# wrt54_relay_board.net
KiCad netlist of a schematic drawn in EAGLE
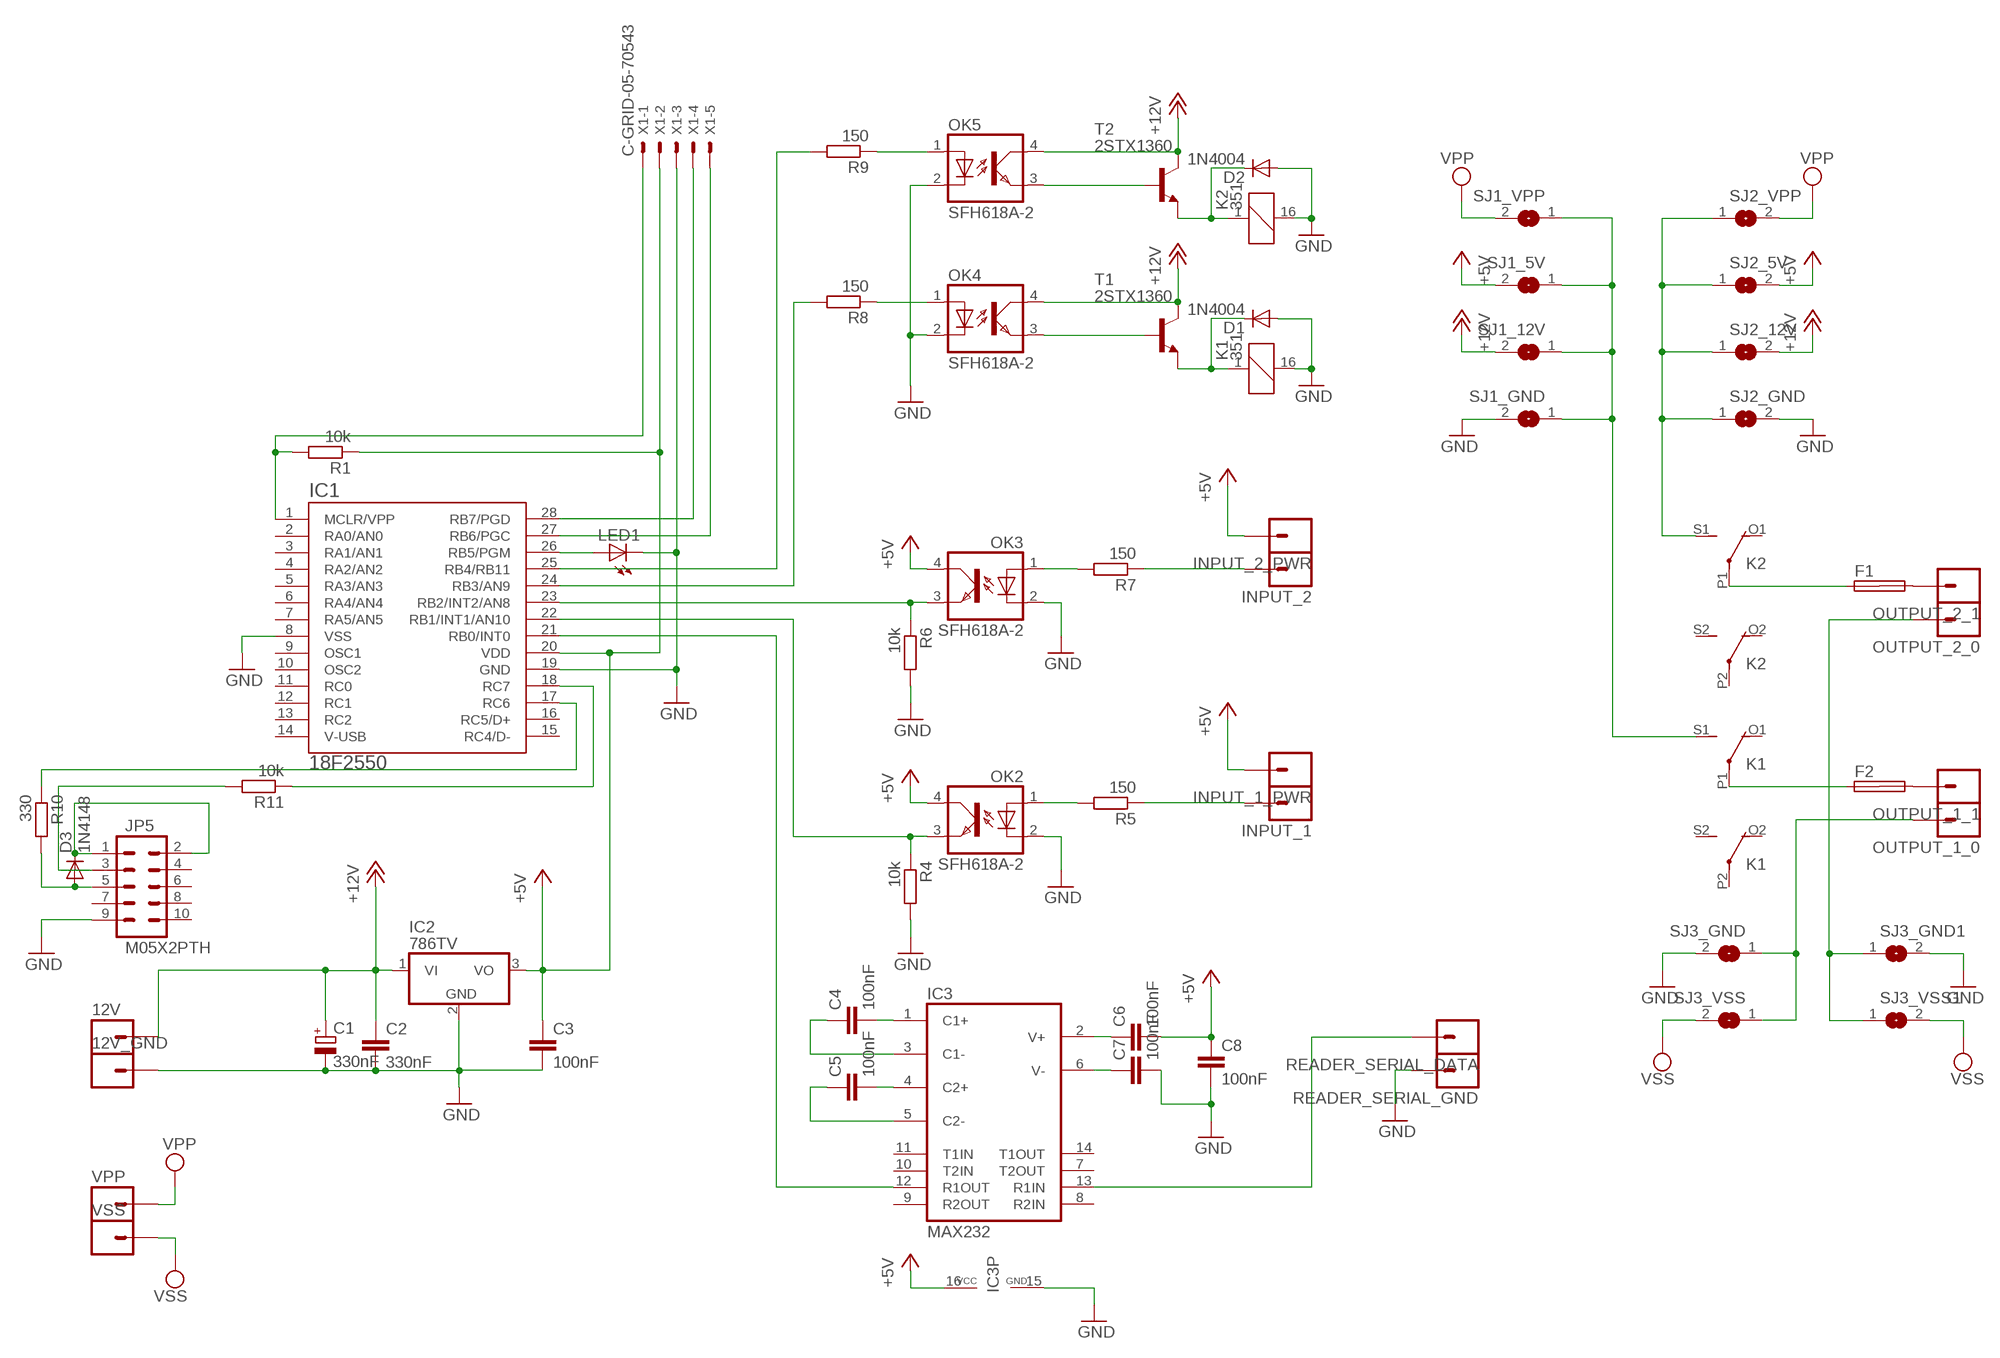
[diagram p0: schematic, sheet 1]

(export (version "E")
  (design (tool "Eeschema 10.0.6"))
  (components
    (comp (ref "12V")
      (value "M01PTH_LONGPAD")
      (footprint "eagle-import:1X01_LONGPAD")
      (libsource (lib "eagle-import") (part "M01PTH_LONGPAD"))
    )
    (comp (ref "12V_GND")
      (value "M01PTH_LONGPAD")
      (footprint "eagle-import:1X01_LONGPAD")
      (libsource (lib "eagle-import") (part "M01PTH_LONGPAD"))
    )
    (comp (ref "C1")
      (value "330nF")
      (footprint "eagle-import:E5-6")
      (libsource (lib "eagle-import") (part "CPOL-EUE5-6"))
    )
    (comp (ref "C2")
      (value "330nF")
      (footprint "eagle-import:C5B2.5")
      (libsource (lib "eagle-import") (part "C5/2.5"))
    )
    (comp (ref "C3")
      (value "100nF")
      (footprint "eagle-import:C5B2.5")
      (libsource (lib "eagle-import") (part "C5/2.5"))
    )
    (comp (ref "C4")
      (value "100nF")
      (footprint "eagle-import:C5B2.5")
      (libsource (lib "eagle-import") (part "C5/2.5"))
    )
    (comp (ref "C5")
      (value "100nF")
      (footprint "eagle-import:C5B2.5")
      (libsource (lib "eagle-import") (part "C5/2.5"))
    )
    (comp (ref "C6")
      (value "100nF")
      (footprint "eagle-import:C5B2.5")
      (libsource (lib "eagle-import") (part "C5/2.5"))
    )
    (comp (ref "C7")
      (value "100nF")
      (footprint "eagle-import:C5B2.5")
      (libsource (lib "eagle-import") (part "C5/2.5"))
    )
    (comp (ref "C8")
      (value "100nF")
      (footprint "eagle-import:C5B2.5")
      (libsource (lib "eagle-import") (part "C5/2.5"))
    )
    (comp (ref "D1")
      (value "1N4004")
      (footprint "eagle-import:DO35-7")
      (libsource (lib "eagle-import") (part "1N4148DO35-7"))
    )
    (comp (ref "D2")
      (value "1N4004")
      (footprint "eagle-import:DO35-7")
      (libsource (lib "eagle-import") (part "1N4148DO35-7"))
    )
    (comp (ref "D3")
      (value "1N4148")
      (footprint "eagle-import:DO35-7")
      (libsource (lib "eagle-import") (part "1N4148DO35-7"))
    )
    (comp (ref "F1")
      (value "SHK20L")
      (footprint "eagle-import:SHK20L")
      (libsource (lib "eagle-import") (part "SHK20L"))
    )
    (comp (ref "F2")
      (value "SHK20L")
      (footprint "eagle-import:SHK20L")
      (libsource (lib "eagle-import") (part "SHK20L"))
    )
    (comp (ref "IC1")
      (value "18F2550")
      (footprint "eagle-import:DIL28")
      (libsource (lib "eagle-import") (part "PIC18F2550DIL-28"))
    )
    (comp (ref "IC2")
      (value "786TV")
      (footprint "eagle-import:TO220V")
      (libsource (lib "eagle-import") (part "78TV6"))
    )
    (comp (ref "IC3")
      (value "MAX232")
      (footprint "eagle-import:DIL16")
      (fields (field (name "MF") "MAXIM") (field (name "MPN") "MAX232ACPE+"))
      (libsource (lib "eagle-import") (part "MAX232"))
    )
    (comp (ref "INPUT_1")
      (value "M01PTH_LONGPAD")
      (footprint "eagle-import:1X01_LONGPAD")
      (libsource (lib "eagle-import") (part "M01PTH_LONGPAD"))
    )
    (comp (ref "INPUT_1_PWR")
      (value "M01PTH_LONGPAD")
      (footprint "eagle-import:1X01_LONGPAD")
      (libsource (lib "eagle-import") (part "M01PTH_LONGPAD"))
    )
    (comp (ref "INPUT_2")
      (value "M01PTH_LONGPAD")
      (footprint "eagle-import:1X01_LONGPAD")
      (libsource (lib "eagle-import") (part "M01PTH_LONGPAD"))
    )
    (comp (ref "INPUT_2_PWR")
      (value "M01PTH_LONGPAD")
      (footprint "eagle-import:1X01_LONGPAD")
      (libsource (lib "eagle-import") (part "M01PTH_LONGPAD"))
    )
    (comp (ref "JP5")
      (value "M05X2PTH")
      (footprint "eagle-import:AVR_ICSP")
      (libsource (lib "eagle-import") (part "M05X2PTH"))
    )
    (comp (ref "K1")
      (value "351")
      (footprint "eagle-import:351")
      (libsource (lib "eagle-import") (part "351"))
    )
    (comp (ref "K2")
      (value "351")
      (footprint "eagle-import:351")
      (libsource (lib "eagle-import") (part "351"))
    )
    (comp (ref "LED1")
      (value "LED5MM")
      (footprint "eagle-import:LED5MM")
      (libsource (lib "eagle-import") (part "LED5MM"))
    )
    (comp (ref "OK2")
      (value "SFH618A-2")
      (footprint "eagle-import:DIP4")
      (libsource (lib "eagle-import") (part "SFH618?A-2"))
    )
    (comp (ref "OK3")
      (value "SFH618A-2")
      (footprint "eagle-import:DIP4")
      (libsource (lib "eagle-import") (part "SFH618?A-2"))
    )
    (comp (ref "OK4")
      (value "SFH618A-2")
      (footprint "eagle-import:DIP4")
      (libsource (lib "eagle-import") (part "SFH618?A-2"))
    )
    (comp (ref "OK5")
      (value "SFH618A-2")
      (footprint "eagle-import:DIP4")
      (libsource (lib "eagle-import") (part "SFH618?A-2"))
    )
    (comp (ref "OUTPUT_1_0")
      (value "M01PTH_LONGPAD")
      (footprint "eagle-import:1X01_LONGPAD")
      (libsource (lib "eagle-import") (part "M01PTH_LONGPAD"))
    )
    (comp (ref "OUTPUT_1_1")
      (value "M01PTH_LONGPAD")
      (footprint "eagle-import:1X01_LONGPAD")
      (libsource (lib "eagle-import") (part "M01PTH_LONGPAD"))
    )
    (comp (ref "OUTPUT_2_0")
      (value "M01PTH_LONGPAD")
      (footprint "eagle-import:1X01_LONGPAD")
      (libsource (lib "eagle-import") (part "M01PTH_LONGPAD"))
    )
    (comp (ref "OUTPUT_2_1")
      (value "M01PTH_LONGPAD")
      (footprint "eagle-import:1X01_LONGPAD")
      (libsource (lib "eagle-import") (part "M01PTH_LONGPAD"))
    )
    (comp (ref "R1")
      (value "10k")
      (footprint "eagle-import:0204_7")
      (libsource (lib "eagle-import") (part "R-EU_0204/7"))
    )
    (comp (ref "R4")
      (value "10k")
      (footprint "eagle-import:0207_10")
      (libsource (lib "eagle-import") (part "R-EU_0207/10"))
    )
    (comp (ref "R5")
      (value "150")
      (footprint "eagle-import:0204V")
      (libsource (lib "eagle-import") (part "R-EU_0204/2V"))
    )
    (comp (ref "R6")
      (value "10k")
      (footprint "eagle-import:0207_10")
      (libsource (lib "eagle-import") (part "R-EU_0207/10"))
    )
    (comp (ref "R7")
      (value "150")
      (footprint "eagle-import:0204V")
      (libsource (lib "eagle-import") (part "R-EU_0204/2V"))
    )
    (comp (ref "R8")
      (value "150")
      (footprint "eagle-import:0204_7")
      (libsource (lib "eagle-import") (part "R-EU_0204/7"))
    )
    (comp (ref "R9")
      (value "150")
      (footprint "eagle-import:0204_7")
      (libsource (lib "eagle-import") (part "R-EU_0204/7"))
    )
    (comp (ref "R10")
      (value "330")
      (footprint "eagle-import:0204V")
      (libsource (lib "eagle-import") (part "R-EU_0204/2V"))
    )
    (comp (ref "R11")
      (value "10k")
      (footprint "eagle-import:0204V")
      (libsource (lib "eagle-import") (part "R-EU_0204/2V"))
    )
    (comp (ref "READER_SERIAL_DATA")
      (value "M01PTH_LONGPAD")
      (footprint "eagle-import:1X01_LONGPAD")
      (libsource (lib "eagle-import") (part "M01PTH_LONGPAD"))
    )
    (comp (ref "READER_SERIAL_GND")
      (value "M01PTH_LONGPAD")
      (footprint "eagle-import:1X01_LONGPAD")
      (libsource (lib "eagle-import") (part "M01PTH_LONGPAD"))
    )
    (comp (ref "SJ1_5V")
      (value "SJW")
      (footprint "eagle-import:SJW")
      (libsource (lib "eagle-import") (part "SJW"))
    )
    (comp (ref "SJ1_12V")
      (value "SJW")
      (footprint "eagle-import:SJW")
      (libsource (lib "eagle-import") (part "SJW"))
    )
    (comp (ref "SJ1_GND")
      (value "SJW")
      (footprint "eagle-import:SJW")
      (libsource (lib "eagle-import") (part "SJW"))
    )
    (comp (ref "SJ1_VPP")
      (value "SJW")
      (footprint "eagle-import:SJW")
      (libsource (lib "eagle-import") (part "SJW"))
    )
    (comp (ref "SJ2_5V")
      (value "SJW")
      (footprint "eagle-import:SJW")
      (libsource (lib "eagle-import") (part "SJW"))
    )
    (comp (ref "SJ2_12V")
      (value "SJW")
      (footprint "eagle-import:SJW")
      (libsource (lib "eagle-import") (part "SJW"))
    )
    (comp (ref "SJ2_GND")
      (value "SJW")
      (footprint "eagle-import:SJW")
      (libsource (lib "eagle-import") (part "SJW"))
    )
    (comp (ref "SJ2_VPP")
      (value "SJW")
      (footprint "eagle-import:SJW")
      (libsource (lib "eagle-import") (part "SJW"))
    )
    (comp (ref "SJ3_GND")
      (value "SJW")
      (footprint "eagle-import:SJW")
      (libsource (lib "eagle-import") (part "SJW"))
    )
    (comp (ref "SJ3_GND1")
      (value "SJW")
      (footprint "eagle-import:SJW")
      (libsource (lib "eagle-import") (part "SJW"))
    )
    (comp (ref "SJ3_VSS")
      (value "SJW")
      (footprint "eagle-import:SJW")
      (libsource (lib "eagle-import") (part "SJW"))
    )
    (comp (ref "SJ3_VSS1")
      (value "SJW")
      (footprint "eagle-import:SJW")
      (libsource (lib "eagle-import") (part "SJW"))
    )
    (comp (ref "T1")
      (value "2STX1360")
      (footprint "eagle-import:TO92-ECB")
      (libsource (lib "eagle-import") (part "2SC1740"))
    )
    (comp (ref "T2")
      (value "2STX1360")
      (footprint "eagle-import:TO92-ECB")
      (libsource (lib "eagle-import") (part "2SC1740"))
    )
    (comp (ref "VPP")
      (value "M01PTH_LONGPAD")
      (footprint "eagle-import:1X01_LONGPAD")
      (libsource (lib "eagle-import") (part "M01PTH_LONGPAD"))
    )
    (comp (ref "VSS")
      (value "M01PTH_LONGPAD")
      (footprint "eagle-import:1X01_LONGPAD")
      (libsource (lib "eagle-import") (part "M01PTH_LONGPAD"))
    )
    (comp (ref "X1")
      (value "C-GRID-05-70543")
      (footprint "eagle-import:70543-05")
      (libsource (lib "eagle-import") (part "C-GRID-05-70543"))
    )
  )
  (nets
    (net (code "1") (name "+5V") (class "Default")
      (node (ref "C3") (pin "1") (pinfunction "1_1") (pintype "passive"))
      (node (ref "C6") (pin "2") (pinfunction "2_2") (pintype "passive"))
      (node (ref "C8") (pin "1") (pinfunction "1_1") (pintype "passive"))
      (node (ref "IC1") (pin "20") (pinfunction "VDD_20") (pintype "bidirectional"))
      (node (ref "IC2") (pin "3") (pinfunction "VO_3") (pintype "passive"))
      (node (ref "IC3") (pin "16") (pinfunction "VCC_16") (pintype "power_in"))
      (node (ref "INPUT_1_PWR") (pin "1") (pinfunction "1_1") (pintype "passive"))
      (node (ref "INPUT_2_PWR") (pin "1") (pinfunction "1_1") (pintype "passive"))
      (node (ref "OK2") (pin "4") (pinfunction "COL_4") (pintype "passive"))
      (node (ref "OK3") (pin "4") (pinfunction "COL_4") (pintype "passive"))
      (node (ref "R1") (pin "1") (pinfunction "1_1") (pintype "passive"))
      (node (ref "SJ1_5V") (pin "2") (pinfunction "2_2") (pintype "passive"))
      (node (ref "SJ2_5V") (pin "2") (pinfunction "2_2") (pintype "passive"))
      (node (ref "X1") (pin "2") (pinfunction "S_2") (pintype "passive"))
    )
    (net (code "2") (name "+12V") (class "Default")
      (node (ref "12V") (pin "1") (pinfunction "1_1") (pintype "passive"))
      (node (ref "C1") (pin "+") (pinfunction "+_+") (pintype "passive"))
      (node (ref "C2") (pin "1") (pinfunction "1_1") (pintype "passive"))
      (node (ref "IC2") (pin "1") (pinfunction "VI_1") (pintype "input"))
      (node (ref "OK4") (pin "4") (pinfunction "COL_4") (pintype "passive"))
      (node (ref "OK5") (pin "4") (pinfunction "COL_4") (pintype "passive"))
      (node (ref "SJ1_12V") (pin "2") (pinfunction "2_2") (pintype "passive"))
      (node (ref "SJ2_12V") (pin "2") (pinfunction "2_2") (pintype "passive"))
      (node (ref "T1") (pin "C") (pinfunction "C_C") (pintype "passive"))
      (node (ref "T2") (pin "C") (pinfunction "C_C") (pintype "passive"))
    )
    (net (code "3") (name "GND") (class "Default")
      (node (ref "12V_GND") (pin "1") (pinfunction "1_1") (pintype "passive"))
      (node (ref "C1") (pin "-") (pinfunction "-_-") (pintype "passive"))
      (node (ref "C2") (pin "2") (pinfunction "2_2") (pintype "passive"))
      (node (ref "C3") (pin "2") (pinfunction "2_2") (pintype "passive"))
      (node (ref "C7") (pin "2") (pinfunction "2_2") (pintype "passive"))
      (node (ref "C8") (pin "2") (pinfunction "2_2") (pintype "passive"))
      (node (ref "D1") (pin "A") (pinfunction "A_A") (pintype "passive"))
      (node (ref "D2") (pin "A") (pinfunction "A_A") (pintype "passive"))
      (node (ref "IC1") (pin "19") (pinfunction "GND_19") (pintype "bidirectional"))
      (node (ref "IC1") (pin "8") (pinfunction "VSS_8") (pintype "bidirectional"))
      (node (ref "IC2") (pin "2") (pinfunction "GND_2") (pintype "passive"))
      (node (ref "IC3") (pin "15") (pinfunction "GND_15") (pintype "power_in"))
      (node (ref "JP5") (pin "9") (pinfunction "9_9") (pintype "passive"))
      (node (ref "K1") (pin "16") (pinfunction "2_16") (pintype "passive"))
      (node (ref "K2") (pin "16") (pinfunction "2_16") (pintype "passive"))
      (node (ref "LED1") (pin "K") (pinfunction "C_K") (pintype "passive"))
      (node (ref "OK2") (pin "2") (pinfunction "C_2") (pintype "passive"))
      (node (ref "OK3") (pin "2") (pinfunction "C_2") (pintype "passive"))
      (node (ref "OK4") (pin "2") (pinfunction "C_2") (pintype "passive"))
      (node (ref "OK5") (pin "2") (pinfunction "C_2") (pintype "passive"))
      (node (ref "R4") (pin "2") (pinfunction "2_2") (pintype "passive"))
      (node (ref "R6") (pin "2") (pinfunction "2_2") (pintype "passive"))
      (node (ref "READER_SERIAL_GND") (pin "1") (pinfunction "1_1") (pintype "passive"))
      (node (ref "SJ1_GND") (pin "2") (pinfunction "2_2") (pintype "passive"))
      (node (ref "SJ2_GND") (pin "2") (pinfunction "2_2") (pintype "passive"))
      (node (ref "SJ3_GND") (pin "2") (pinfunction "2_2") (pintype "passive"))
      (node (ref "SJ3_GND1") (pin "2") (pinfunction "2_2") (pintype "passive"))
      (node (ref "X1") (pin "3") (pinfunction "S_3") (pintype "passive"))
    )
    (net (code "4") (name "Net-(D1-PadC)") (class "Default")
      (node (ref "D1") (pin "C") (pinfunction "C_C") (pintype "passive"))
      (node (ref "K1") (pin "1") (pinfunction "1_1") (pintype "passive"))
      (node (ref "T1") (pin "E") (pinfunction "E_E") (pintype "passive"))
    )
    (net (code "5") (name "Net-(D2-PadC)") (class "Default")
      (node (ref "D2") (pin "C") (pinfunction "C_C") (pintype "passive"))
      (node (ref "K2") (pin "1") (pinfunction "1_1") (pintype "passive"))
      (node (ref "T2") (pin "E") (pinfunction "E_E") (pintype "passive"))
    )
    (net (code "6") (name "Net-(D3-PadA)") (class "Default")
      (node (ref "D3") (pin "A") (pinfunction "A_A") (pintype "passive"))
      (node (ref "JP5") (pin "5") (pinfunction "5_5") (pintype "passive"))
      (node (ref "R10") (pin "2") (pinfunction "2_2") (pintype "passive"))
    )
    (net (code "7") (name "Net-(D3-PadC)") (class "Default")
      (node (ref "D3") (pin "C") (pinfunction "C_C") (pintype "passive"))
      (node (ref "JP5") (pin "1") (pinfunction "1_1") (pintype "passive"))
      (node (ref "JP5") (pin "2") (pinfunction "2_2") (pintype "passive"))
    )
    (net (code "8") (name "Net-(F1-Pad2A)") (class "Default")
      (node (ref "F1") (pin "2A") (pinfunction "2A_2A") (pintype "passive"))
      (node (ref "OUTPUT_2_1") (pin "1") (pinfunction "1_1") (pintype "passive"))
    )
    (net (code "9") (name "Net-(F2-Pad2A)") (class "Default")
      (node (ref "F2") (pin "2A") (pinfunction "2A_2A") (pintype "passive"))
      (node (ref "OUTPUT_1_1") (pin "1") (pinfunction "1_1") (pintype "passive"))
    )
    (net (code "10") (name "Net-(IC1-MCLR{slash}VPP)") (class "Default")
      (node (ref "IC1") (pin "1") (pinfunction "MCLR/VPP_1") (pintype "bidirectional"))
      (node (ref "R1") (pin "2") (pinfunction "2_2") (pintype "passive"))
      (node (ref "X1") (pin "1") (pinfunction "S_1") (pintype "passive"))
    )
    (net (code "11") (name "Net-(IC1-RB0{slash}INT0)") (class "Default")
      (node (ref "IC1") (pin "21") (pinfunction "RB0/INT0_21") (pintype "bidirectional"))
      (node (ref "IC3") (pin "12") (pinfunction "R1OUT_12") (pintype "output"))
    )
    (net (code "12") (name "Net-(IC1-RB1{slash}INT1{slash}AN10)") (class "Default")
      (node (ref "IC1") (pin "22") (pinfunction "RB1/INT1/AN10_22") (pintype "bidirectional"))
      (node (ref "OK2") (pin "3") (pinfunction "EMIT_3") (pintype "passive"))
      (node (ref "R4") (pin "1") (pinfunction "1_1") (pintype "passive"))
    )
    (net (code "13") (name "Net-(IC1-RB2{slash}INT2{slash}AN8)") (class "Default")
      (node (ref "IC1") (pin "23") (pinfunction "RB2/INT2/AN8_23") (pintype "bidirectional"))
      (node (ref "OK3") (pin "3") (pinfunction "EMIT_3") (pintype "passive"))
      (node (ref "R6") (pin "1") (pinfunction "1_1") (pintype "passive"))
    )
    (net (code "14") (name "Net-(IC1-RB3{slash}AN9)") (class "Default")
      (node (ref "IC1") (pin "24") (pinfunction "RB3/AN9_24") (pintype "bidirectional"))
      (node (ref "R8") (pin "2") (pinfunction "2_2") (pintype "passive"))
    )
    (net (code "15") (name "Net-(IC1-RB4{slash}RB11)") (class "Default")
      (node (ref "IC1") (pin "25") (pinfunction "RB4/RB11_25") (pintype "bidirectional"))
      (node (ref "R9") (pin "2") (pinfunction "2_2") (pintype "passive"))
    )
    (net (code "16") (name "Net-(IC1-RB5{slash}PGM)") (class "Default")
      (node (ref "IC1") (pin "26") (pinfunction "RB5/PGM_26") (pintype "bidirectional"))
      (node (ref "LED1") (pin "A") (pinfunction "A_A") (pintype "passive"))
    )
    (net (code "17") (name "Net-(IC1-RB6{slash}PGC)") (class "Default")
      (node (ref "IC1") (pin "27") (pinfunction "RB6/PGC_27") (pintype "bidirectional"))
      (node (ref "X1") (pin "5") (pinfunction "S_5") (pintype "passive"))
    )
    (net (code "18") (name "Net-(IC1-RB7{slash}PGD)") (class "Default")
      (node (ref "IC1") (pin "28") (pinfunction "RB7/PGD_28") (pintype "bidirectional"))
      (node (ref "X1") (pin "4") (pinfunction "S_4") (pintype "passive"))
    )
    (net (code "19") (name "Net-(IC1-RC6)") (class "Default")
      (node (ref "IC1") (pin "17") (pinfunction "RC6_17") (pintype "bidirectional"))
      (node (ref "R10") (pin "1") (pinfunction "1_1") (pintype "passive"))
    )
    (net (code "20") (name "Net-(IC1-RC7)") (class "Default")
      (node (ref "IC1") (pin "18") (pinfunction "RC7_18") (pintype "bidirectional"))
      (node (ref "R11") (pin "1") (pinfunction "1_1") (pintype "passive"))
    )
    (net (code "21") (name "Net-(IC3A-C1+)") (class "Default")
      (node (ref "C4") (pin "2") (pinfunction "2_2") (pintype "passive"))
      (node (ref "IC3") (pin "1") (pinfunction "C1+_1") (pintype "bidirectional"))
    )
    (net (code "22") (name "Net-(IC3A-C1-)") (class "Default")
      (node (ref "C4") (pin "1") (pinfunction "1_1") (pintype "passive"))
      (node (ref "IC3") (pin "3") (pinfunction "C1-_3") (pintype "bidirectional"))
    )
    (net (code "23") (name "Net-(IC3A-C2+)") (class "Default")
      (node (ref "C5") (pin "2") (pinfunction "2_2") (pintype "passive"))
      (node (ref "IC3") (pin "4") (pinfunction "C2+_4") (pintype "bidirectional"))
    )
    (net (code "24") (name "Net-(IC3A-C2-)") (class "Default")
      (node (ref "C5") (pin "1") (pinfunction "1_1") (pintype "passive"))
      (node (ref "IC3") (pin "5") (pinfunction "C2-_5") (pintype "bidirectional"))
    )
    (net (code "25") (name "Net-(IC3A-R1IN)") (class "Default")
      (node (ref "IC3") (pin "13") (pinfunction "R1IN_13") (pintype "input"))
      (node (ref "READER_SERIAL_DATA") (pin "1") (pinfunction "1_1") (pintype "passive"))
    )
    (net (code "26") (name "Net-(IC3A-V+)") (class "Default")
      (node (ref "C6") (pin "1") (pinfunction "1_1") (pintype "passive"))
      (node (ref "IC3") (pin "2") (pinfunction "V+_2") (pintype "bidirectional"))
    )
    (net (code "27") (name "Net-(IC3A-V-)") (class "Default")
      (node (ref "C7") (pin "1") (pinfunction "1_1") (pintype "passive"))
      (node (ref "IC3") (pin "6") (pinfunction "V-_6") (pintype "bidirectional"))
    )
    (net (code "28") (name "Net-(INPUT_1-Pad1)") (class "Default")
      (node (ref "INPUT_1") (pin "1") (pinfunction "1_1") (pintype "passive"))
      (node (ref "R5") (pin "1") (pinfunction "1_1") (pintype "passive"))
    )
    (net (code "29") (name "Net-(INPUT_2-Pad1)") (class "Default")
      (node (ref "INPUT_2") (pin "1") (pinfunction "1_1") (pintype "passive"))
      (node (ref "R7") (pin "1") (pinfunction "1_1") (pintype "passive"))
    )
    (net (code "30") (name "Net-(JP5-Pad3)") (class "Default")
      (node (ref "JP5") (pin "3") (pinfunction "3_3") (pintype "passive"))
      (node (ref "R11") (pin "2") (pinfunction "2_2") (pintype "passive"))
    )
    (net (code "31") (name "Net-(K1B-P)") (class "Default")
      (node (ref "F2") (pin "1A") (pinfunction "1A_1A") (pintype "passive"))
      (node (ref "K1") (pin "P1") (pinfunction "P_P1") (pintype "passive"))
    )
    (net (code "32") (name "Net-(K1B-S)") (class "Default")
      (node (ref "K1") (pin "S1") (pinfunction "S_S1") (pintype "passive"))
      (node (ref "SJ1_12V") (pin "1") (pinfunction "1_1") (pintype "passive"))
      (node (ref "SJ1_5V") (pin "1") (pinfunction "1_1") (pintype "passive"))
      (node (ref "SJ1_GND") (pin "1") (pinfunction "1_1") (pintype "passive"))
      (node (ref "SJ1_VPP") (pin "1") (pinfunction "1_1") (pintype "passive"))
    )
    (net (code "33") (name "Net-(K2B-P)") (class "Default")
      (node (ref "F1") (pin "1A") (pinfunction "1A_1A") (pintype "passive"))
      (node (ref "K2") (pin "P1") (pinfunction "P_P1") (pintype "passive"))
    )
    (net (code "34") (name "Net-(K2B-S)") (class "Default")
      (node (ref "K2") (pin "S1") (pinfunction "S_S1") (pintype "passive"))
      (node (ref "SJ2_12V") (pin "1") (pinfunction "1_1") (pintype "passive"))
      (node (ref "SJ2_5V") (pin "1") (pinfunction "1_1") (pintype "passive"))
      (node (ref "SJ2_GND") (pin "1") (pinfunction "1_1") (pintype "passive"))
      (node (ref "SJ2_VPP") (pin "1") (pinfunction "1_1") (pintype "passive"))
    )
    (net (code "35") (name "Net-(OK2-A)") (class "Default")
      (node (ref "OK2") (pin "1") (pinfunction "A_1") (pintype "passive"))
      (node (ref "R5") (pin "2") (pinfunction "2_2") (pintype "passive"))
    )
    (net (code "36") (name "Net-(OK3-A)") (class "Default")
      (node (ref "OK3") (pin "1") (pinfunction "A_1") (pintype "passive"))
      (node (ref "R7") (pin "2") (pinfunction "2_2") (pintype "passive"))
    )
    (net (code "37") (name "Net-(OK4-A)") (class "Default")
      (node (ref "OK4") (pin "1") (pinfunction "A_1") (pintype "passive"))
      (node (ref "R8") (pin "1") (pinfunction "1_1") (pintype "passive"))
    )
    (net (code "38") (name "Net-(OK4-EMIT)") (class "Default")
      (node (ref "OK4") (pin "3") (pinfunction "EMIT_3") (pintype "passive"))
      (node (ref "T1") (pin "B") (pinfunction "B_B") (pintype "passive"))
    )
    (net (code "39") (name "Net-(OK5-A)") (class "Default")
      (node (ref "OK5") (pin "1") (pinfunction "A_1") (pintype "passive"))
      (node (ref "R9") (pin "1") (pinfunction "1_1") (pintype "passive"))
    )
    (net (code "40") (name "Net-(OK5-EMIT)") (class "Default")
      (node (ref "OK5") (pin "3") (pinfunction "EMIT_3") (pintype "passive"))
      (node (ref "T2") (pin "B") (pinfunction "B_B") (pintype "passive"))
    )
    (net (code "41") (name "Net-(OUTPUT_1_0-Pad1)") (class "Default")
      (node (ref "OUTPUT_1_0") (pin "1") (pinfunction "1_1") (pintype "passive"))
      (node (ref "SJ3_GND") (pin "1") (pinfunction "1_1") (pintype "passive"))
      (node (ref "SJ3_VSS") (pin "1") (pinfunction "1_1") (pintype "passive"))
    )
    (net (code "42") (name "Net-(OUTPUT_2_0-Pad1)") (class "Default")
      (node (ref "OUTPUT_2_0") (pin "1") (pinfunction "1_1") (pintype "passive"))
      (node (ref "SJ3_GND1") (pin "1") (pinfunction "1_1") (pintype "passive"))
      (node (ref "SJ3_VSS1") (pin "1") (pinfunction "1_1") (pintype "passive"))
    )
    (net (code "43") (name "VPP") (class "Default")
      (node (ref "SJ1_VPP") (pin "2") (pinfunction "2_2") (pintype "passive"))
      (node (ref "SJ2_VPP") (pin "2") (pinfunction "2_2") (pintype "passive"))
      (node (ref "VPP") (pin "1") (pinfunction "1_1") (pintype "passive"))
    )
    (net (code "44") (name "VSS") (class "Default")
      (node (ref "SJ3_VSS") (pin "2") (pinfunction "2_2") (pintype "passive"))
      (node (ref "SJ3_VSS1") (pin "2") (pinfunction "2_2") (pintype "passive"))
      (node (ref "VSS") (pin "1") (pinfunction "1_1") (pintype "passive"))
    )
    (net (code "45") (name "unconnected-(F1-Pad1B)") (class "Default")
      (node (ref "F1") (pin "1B") (pinfunction "1B_1B") (pintype "passive"))
    )
    (net (code "46") (name "unconnected-(F1-Pad2B)") (class "Default")
      (node (ref "F1") (pin "2B") (pinfunction "2B_2B") (pintype "passive"))
    )
    (net (code "47") (name "unconnected-(F2-Pad1B)") (class "Default")
      (node (ref "F2") (pin "1B") (pinfunction "1B_1B") (pintype "passive"))
    )
    (net (code "48") (name "unconnected-(F2-Pad2B)") (class "Default")
      (node (ref "F2") (pin "2B") (pinfunction "2B_2B") (pintype "passive"))
    )
    (net (code "49") (name "unconnected-(IC1-OSC1-Pad9)") (class "Default")
      (node (ref "IC1") (pin "9") (pinfunction "OSC1_9") (pintype "bidirectional"))
    )
    (net (code "50") (name "unconnected-(IC1-OSC2-Pad10)") (class "Default")
      (node (ref "IC1") (pin "10") (pinfunction "OSC2_10") (pintype "bidirectional"))
    )
    (net (code "51") (name "unconnected-(IC1-RA0{slash}AN0-Pad2)") (class "Default")
      (node (ref "IC1") (pin "2") (pinfunction "RA0/AN0_2") (pintype "bidirectional"))
    )
    (net (code "52") (name "unconnected-(IC1-RA1{slash}AN1-Pad3)") (class "Default")
      (node (ref "IC1") (pin "3") (pinfunction "RA1/AN1_3") (pintype "bidirectional"))
    )
    (net (code "53") (name "unconnected-(IC1-RA2{slash}AN2-Pad4)") (class "Default")
      (node (ref "IC1") (pin "4") (pinfunction "RA2/AN2_4") (pintype "bidirectional"))
    )
    (net (code "54") (name "unconnected-(IC1-RA3{slash}AN3-Pad5)") (class "Default")
      (node (ref "IC1") (pin "5") (pinfunction "RA3/AN3_5") (pintype "bidirectional"))
    )
    (net (code "55") (name "unconnected-(IC1-RA4{slash}AN4-Pad6)") (class "Default")
      (node (ref "IC1") (pin "6") (pinfunction "RA4/AN4_6") (pintype "bidirectional"))
    )
    (net (code "56") (name "unconnected-(IC1-RA5{slash}AN5-Pad7)") (class "Default")
      (node (ref "IC1") (pin "7") (pinfunction "RA5/AN5_7") (pintype "bidirectional"))
    )
    (net (code "57") (name "unconnected-(IC1-RC0-Pad11)") (class "Default")
      (node (ref "IC1") (pin "11") (pinfunction "RC0_11") (pintype "bidirectional"))
    )
    (net (code "58") (name "unconnected-(IC1-RC1-Pad12)") (class "Default")
      (node (ref "IC1") (pin "12") (pinfunction "RC1_12") (pintype "bidirectional"))
    )
    (net (code "59") (name "unconnected-(IC1-RC2-Pad13)") (class "Default")
      (node (ref "IC1") (pin "13") (pinfunction "RC2_13") (pintype "bidirectional"))
    )
    (net (code "60") (name "unconnected-(IC1-RC4{slash}D--Pad15)") (class "Default")
      (node (ref "IC1") (pin "15") (pinfunction "RC4/D-_15") (pintype "bidirectional"))
    )
    (net (code "61") (name "unconnected-(IC1-RC5{slash}D+-Pad16)") (class "Default")
      (node (ref "IC1") (pin "16") (pinfunction "RC5/D+_16") (pintype "bidirectional"))
    )
    (net (code "62") (name "unconnected-(IC1-V-USB-Pad14)") (class "Default")
      (node (ref "IC1") (pin "14") (pinfunction "V-USB_14") (pintype "bidirectional"))
    )
    (net (code "63") (name "unconnected-(IC3A-R2IN-Pad8)") (class "Default")
      (node (ref "IC3") (pin "8") (pinfunction "R2IN_8") (pintype "input"))
    )
    (net (code "64") (name "unconnected-(IC3A-R2OUT-Pad9)") (class "Default")
      (node (ref "IC3") (pin "9") (pinfunction "R2OUT_9") (pintype "output"))
    )
    (net (code "65") (name "unconnected-(IC3A-T1IN-Pad11)") (class "Default")
      (node (ref "IC3") (pin "11") (pinfunction "T1IN_11") (pintype "input"))
    )
    (net (code "66") (name "unconnected-(IC3A-T1OUT-Pad14)") (class "Default")
      (node (ref "IC3") (pin "14") (pinfunction "T1OUT_14") (pintype "output"))
    )
    (net (code "67") (name "unconnected-(IC3A-T2IN-Pad10)") (class "Default")
      (node (ref "IC3") (pin "10") (pinfunction "T2IN_10") (pintype "input"))
    )
    (net (code "68") (name "unconnected-(IC3A-T2OUT-Pad7)") (class "Default")
      (node (ref "IC3") (pin "7") (pinfunction "T2OUT_7") (pintype "output"))
    )
    (net (code "69") (name "unconnected-(JP5-Pad4)") (class "Default")
      (node (ref "JP5") (pin "4") (pinfunction "4_4") (pintype "passive"))
    )
    (net (code "70") (name "unconnected-(JP5-Pad6)") (class "Default")
      (node (ref "JP5") (pin "6") (pinfunction "6_6") (pintype "passive"))
    )
    (net (code "71") (name "unconnected-(JP5-Pad7)") (class "Default")
      (node (ref "JP5") (pin "7") (pinfunction "7_7") (pintype "passive"))
    )
    (net (code "72") (name "unconnected-(JP5-Pad8)") (class "Default")
      (node (ref "JP5") (pin "8") (pinfunction "8_8") (pintype "passive"))
    )
    (net (code "73") (name "unconnected-(JP5-Pad10)") (class "Default")
      (node (ref "JP5") (pin "10") (pinfunction "10_10") (pintype "passive"))
    )
    (net (code "74") (name "unconnected-(K1B-O-PadO1)") (class "Default")
      (node (ref "K1") (pin "O1") (pinfunction "O_O1") (pintype "passive"))
    )
    (net (code "75") (name "unconnected-(K1C-O-PadO2)") (class "Default")
      (node (ref "K1") (pin "O2") (pinfunction "O_O2") (pintype "passive"))
    )
    (net (code "76") (name "unconnected-(K1C-P-PadP2)") (class "Default")
      (node (ref "K1") (pin "P2") (pinfunction "P_P2") (pintype "passive"))
    )
    (net (code "77") (name "unconnected-(K1C-S-PadS2)") (class "Default")
      (node (ref "K1") (pin "S2") (pinfunction "S_S2") (pintype "passive"))
    )
    (net (code "78") (name "unconnected-(K2B-O-PadO1)") (class "Default")
      (node (ref "K2") (pin "O1") (pinfunction "O_O1") (pintype "passive"))
    )
    (net (code "79") (name "unconnected-(K2C-O-PadO2)") (class "Default")
      (node (ref "K2") (pin "O2") (pinfunction "O_O2") (pintype "passive"))
    )
    (net (code "80") (name "unconnected-(K2C-P-PadP2)") (class "Default")
      (node (ref "K2") (pin "P2") (pinfunction "P_P2") (pintype "passive"))
    )
    (net (code "81") (name "unconnected-(K2C-S-PadS2)") (class "Default")
      (node (ref "K2") (pin "S2") (pinfunction "S_S2") (pintype "passive"))
    )
  )
)
